# can_shield_simplified.net
KiCad netlist of a schematic drawn in EAGLE
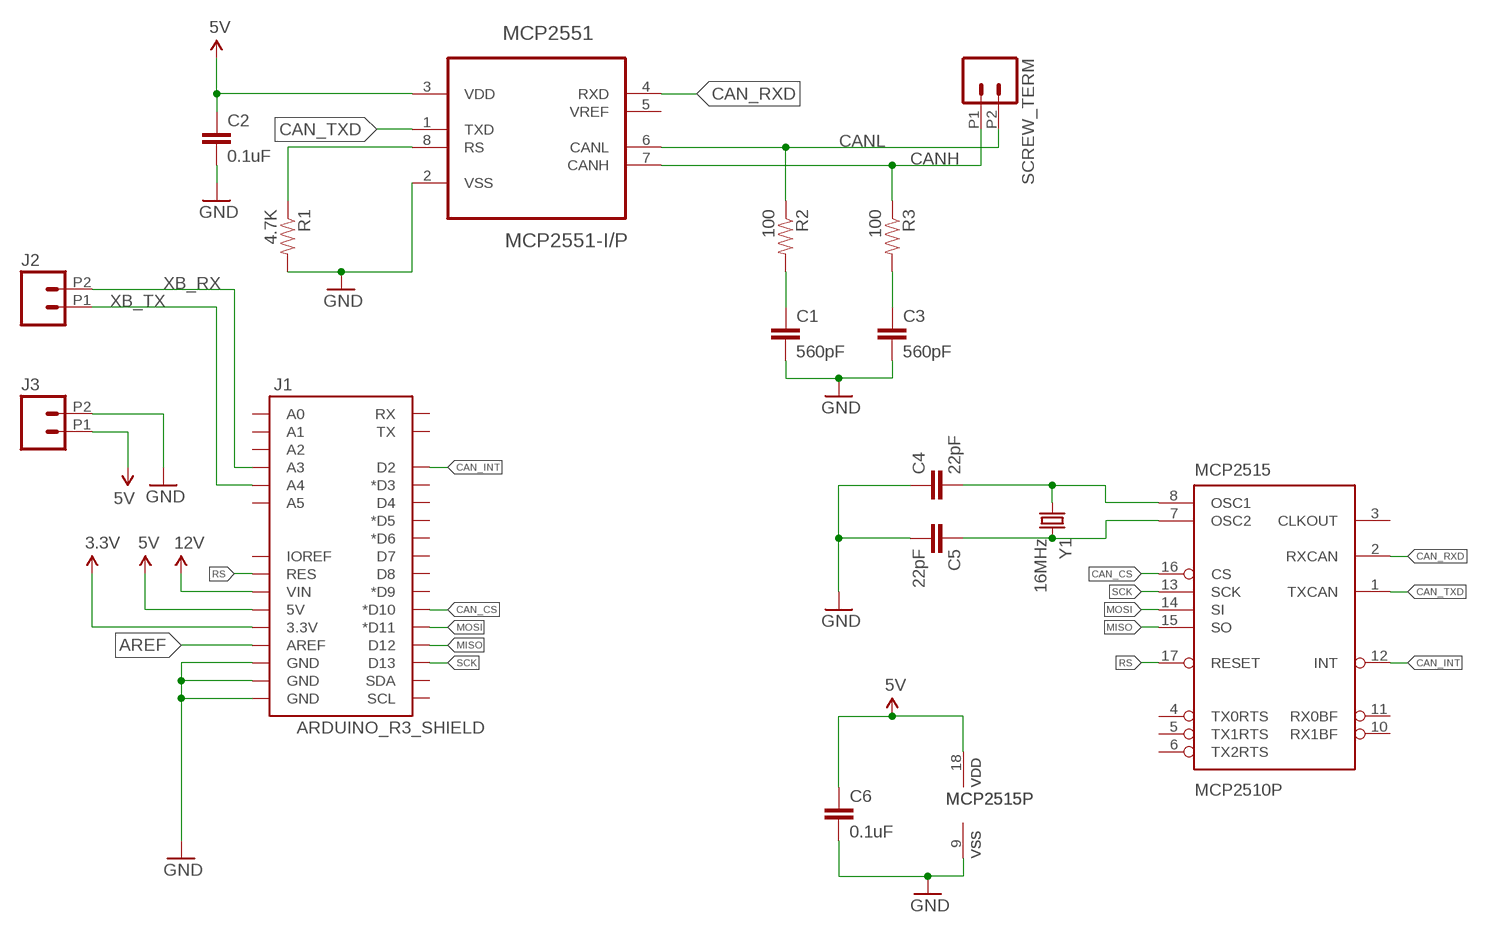
[diagram p0: schematic, sheet 1]

(export (version "E")
  (design (tool "Eeschema 10.0.6"))
  (components
    (comp (ref "C1")
      (value "560pF")
      (footprint "eagle-import:CAP-PTH-SMALL")
      (libsource (lib "eagle-import") (part "CAPPTH"))
    )
    (comp (ref "C2")
      (value "0.1uF")
      (footprint "eagle-import:CAP-PTH-SMALL")
      (libsource (lib "eagle-import") (part "CAPPTH"))
    )
    (comp (ref "C3")
      (value "560pF")
      (footprint "eagle-import:CAP-PTH-SMALL")
      (libsource (lib "eagle-import") (part "CAPPTH"))
    )
    (comp (ref "C4")
      (value "22pF")
      (footprint "eagle-import:CAP-PTH-SMALL")
      (libsource (lib "eagle-import") (part "CAPPTH"))
    )
    (comp (ref "C5")
      (value "22pF")
      (footprint "eagle-import:CAP-PTH-SMALL")
      (libsource (lib "eagle-import") (part "CAPPTH"))
    )
    (comp (ref "C6")
      (value "0.1uF")
      (footprint "eagle-import:CAP-PTH-SMALL")
      (libsource (lib "eagle-import") (part "CAPPTH"))
    )
    (comp (ref "J1")
      (value "ARDUINO_R3_SHIELD")
      (footprint "eagle-import:UNO_R3_SHIELD")
      (libsource (lib "eagle-import") (part "ARDUINO_R3_SHIELD"))
    )
    (comp (ref "J2")
      (value "M022.54MM_SCREWTERM")
      (footprint "eagle-import:1X02_2.54_SCREWTERM")
      (libsource (lib "eagle-import") (part "M022.54MM_SCREWTERM"))
    )
    (comp (ref "J3")
      (value "M022.54MM_SCREWTERM")
      (footprint "eagle-import:1X02_2.54_SCREWTERM")
      (libsource (lib "eagle-import") (part "M022.54MM_SCREWTERM"))
    )
    (comp (ref "MCP2515")
      (value "MCP2510P")
      (footprint "eagle-import:DIL18")
      (libsource (lib "eagle-import") (part "MCP2510P"))
    )
    (comp (ref "MCP2551")
      (value "MCP2551-I/P")
      (footprint "eagle-import:DIP254P762X432-8")
      (libsource (lib "eagle-import") (part "MCP2551-I/P"))
    )
    (comp (ref "R1")
      (value "4.7K")
      (footprint "eagle-import:AXIAL-0.3")
      (libsource (lib "eagle-import") (part "RESISTORAXIAL-0.3"))
    )
    (comp (ref "R2")
      (value "100")
      (footprint "eagle-import:AXIAL-0.3")
      (libsource (lib "eagle-import") (part "RESISTORAXIAL-0.3"))
    )
    (comp (ref "R3")
      (value "100")
      (footprint "eagle-import:AXIAL-0.3")
      (libsource (lib "eagle-import") (part "RESISTORAXIAL-0.3"))
    )
    (comp (ref "SCREW_TERM")
      (value "M022.54MM_SCREWTERM")
      (footprint "eagle-import:1X02_2.54_SCREWTERM")
      (libsource (lib "eagle-import") (part "M022.54MM_SCREWTERM"))
    )
    (comp (ref "Y1")
      (value "16MHz")
      (footprint "eagle-import:HC49US")
      (libsource (lib "eagle-import") (part "CRYSTALHC49US"))
    )
  )
  (nets
    (net (code "1") (name "/CANH") (class "Default")
      (node (ref "MCP2551") (pin "7") (pinfunction "CANH_7") (pintype "bidirectional"))
      (node (ref "R3") (pin "P$1") (pinfunction "1_P$1") (pintype "passive"))
      (node (ref "SCREW_TERM") (pin "P1") (pinfunction "1_P1") (pintype "passive"))
    )
    (net (code "2") (name "/CANL") (class "Default")
      (node (ref "MCP2551") (pin "6") (pinfunction "CANL_6") (pintype "bidirectional"))
      (node (ref "R2") (pin "P$1") (pinfunction "1_P$1") (pintype "passive"))
      (node (ref "SCREW_TERM") (pin "P2") (pinfunction "2_P2") (pintype "passive"))
    )
    (net (code "3") (name "/XB_RX") (class "Default")
      (node (ref "J1") (pin "A3") (pinfunction "A3_A3") (pintype "bidirectional"))
      (node (ref "J2") (pin "P2") (pinfunction "2_P2") (pintype "passive"))
    )
    (net (code "4") (name "/XB_TX") (class "Default")
      (node (ref "J1") (pin "A4") (pinfunction "A4_A4") (pintype "bidirectional"))
      (node (ref "J2") (pin "P1") (pinfunction "1_P1") (pintype "passive"))
    )
    (net (code "5") (name "3.3V") (class "Default")
      (node (ref "J1") (pin "3.3V") (pinfunction "3.3V_3.3V") (pintype "bidirectional"))
    )
    (net (code "6") (name "5V") (class "Default")
      (node (ref "C2") (pin "1") (pinfunction "1_1") (pintype "passive"))
      (node (ref "C6") (pin "1") (pinfunction "1_1") (pintype "passive"))
      (node (ref "J1") (pin "5V") (pinfunction "5V_5V") (pintype "bidirectional"))
      (node (ref "J3") (pin "P1") (pinfunction "1_P1") (pintype "passive"))
      (node (ref "MCP2515") (pin "18") (pinfunction "VDD_18") (pintype "power_in"))
      (node (ref "MCP2551") (pin "3") (pinfunction "VDD_3") (pintype "power_in"))
    )
    (net (code "7") (name "12V") (class "Default")
      (node (ref "J1") (pin "VIN") (pinfunction "VIN_VIN") (pintype "bidirectional"))
    )
    (net (code "8") (name "AREF") (class "Default")
      (node (ref "J1") (pin "AREF") (pinfunction "AREF_AREF") (pintype "bidirectional"))
    )
    (net (code "9") (name "CAN_CS") (class "Default")
      (node (ref "J1") (pin "D10") (pinfunction "*D10_D10") (pintype "bidirectional"))
      (node (ref "MCP2515") (pin "16") (pinfunction "CS_16") (pintype "input"))
    )
    (net (code "10") (name "CAN_INT") (class "Default")
      (node (ref "J1") (pin "D2") (pinfunction "D2_D2") (pintype "bidirectional"))
      (node (ref "MCP2515") (pin "12") (pinfunction "INT_12") (pintype "output"))
    )
    (net (code "11") (name "CAN_RXD") (class "Default")
      (node (ref "MCP2515") (pin "2") (pinfunction "RXCAN_2") (pintype "input"))
      (node (ref "MCP2551") (pin "4") (pinfunction "RXD_4") (pintype "output"))
    )
    (net (code "12") (name "CAN_TXD") (class "Default")
      (node (ref "MCP2515") (pin "1") (pinfunction "TXCAN_1") (pintype "output"))
      (node (ref "MCP2551") (pin "1") (pinfunction "TXD_1") (pintype "input"))
    )
    (net (code "13") (name "GND") (class "Default")
      (node (ref "C1") (pin "2") (pinfunction "2_2") (pintype "passive"))
      (node (ref "C2") (pin "2") (pinfunction "2_2") (pintype "passive"))
      (node (ref "C3") (pin "2") (pinfunction "2_2") (pintype "passive"))
      (node (ref "C4") (pin "1") (pinfunction "1_1") (pintype "passive"))
      (node (ref "C5") (pin "2") (pinfunction "2_2") (pintype "passive"))
      (node (ref "C6") (pin "2") (pinfunction "2_2") (pintype "passive"))
      (node (ref "J1") (pin "GND@0") (pinfunction "GND_GND@0") (pintype "bidirectional"))
      (node (ref "J1") (pin "GND@1") (pinfunction "GND_GND@1") (pintype "bidirectional"))
      (node (ref "J1") (pin "GND@2") (pinfunction "GND_GND@2") (pintype "bidirectional"))
      (node (ref "J3") (pin "P2") (pinfunction "2_P2") (pintype "passive"))
      (node (ref "MCP2515") (pin "9") (pinfunction "VSS_9") (pintype "power_in"))
      (node (ref "MCP2551") (pin "2") (pinfunction "VSS_2") (pintype "power_in"))
      (node (ref "R1") (pin "P$2") (pinfunction "2_P$2") (pintype "passive"))
    )
    (net (code "14") (name "MISO") (class "Default")
      (node (ref "J1") (pin "D12") (pinfunction "D12_D12") (pintype "bidirectional"))
      (node (ref "MCP2515") (pin "15") (pinfunction "SO_15") (pintype "output"))
    )
    (net (code "15") (name "MOSI") (class "Default")
      (node (ref "J1") (pin "D11") (pinfunction "*D11_D11") (pintype "bidirectional"))
      (node (ref "MCP2515") (pin "14") (pinfunction "SI_14") (pintype "input"))
    )
    (net (code "16") (name "Net-(MCP2515A-OSC1)") (class "Default")
      (node (ref "C4") (pin "2") (pinfunction "2_2") (pintype "passive"))
      (node (ref "MCP2515") (pin "8") (pinfunction "OSC1_8") (pintype "input"))
      (node (ref "Y1") (pin "1") (pinfunction "1_1") (pintype "passive"))
    )
    (net (code "17") (name "Net-(MCP2515A-OSC2)") (class "Default")
      (node (ref "C5") (pin "1") (pinfunction "1_1") (pintype "passive"))
      (node (ref "MCP2515") (pin "7") (pinfunction "OSC2_7") (pintype "output"))
      (node (ref "Y1") (pin "2") (pinfunction "2_2") (pintype "passive"))
    )
    (net (code "18") (name "Net-(MCP2551-RS)") (class "Default")
      (node (ref "MCP2551") (pin "8") (pinfunction "RS_8") (pintype "input"))
      (node (ref "R1") (pin "P$1") (pinfunction "1_P$1") (pintype "passive"))
    )
    (net (code "19") (name "Net-(R2-2)") (class "Default")
      (node (ref "C1") (pin "1") (pinfunction "1_1") (pintype "passive"))
      (node (ref "R2") (pin "P$2") (pinfunction "2_P$2") (pintype "passive"))
    )
    (net (code "20") (name "Net-(R3-2)") (class "Default")
      (node (ref "C3") (pin "1") (pinfunction "1_1") (pintype "passive"))
      (node (ref "R3") (pin "P$2") (pinfunction "2_P$2") (pintype "passive"))
    )
    (net (code "21") (name "RS") (class "Default")
      (node (ref "J1") (pin "RES") (pinfunction "RES_RES") (pintype "bidirectional"))
      (node (ref "MCP2515") (pin "17") (pinfunction "RESET_17") (pintype "input"))
    )
    (net (code "22") (name "SCK") (class "Default")
      (node (ref "J1") (pin "D13") (pinfunction "D13_D13") (pintype "bidirectional"))
      (node (ref "MCP2515") (pin "13") (pinfunction "SCK_13") (pintype "input"))
    )
    (net (code "23") (name "unconnected-(J1-*D3-PadD3)") (class "Default")
      (node (ref "J1") (pin "D3") (pinfunction "*D3_D3") (pintype "bidirectional"))
    )
    (net (code "24") (name "unconnected-(J1-*D5-PadD5)") (class "Default")
      (node (ref "J1") (pin "D5") (pinfunction "*D5_D5") (pintype "bidirectional"))
    )
    (net (code "25") (name "unconnected-(J1-*D6-PadD6)") (class "Default")
      (node (ref "J1") (pin "D6") (pinfunction "*D6_D6") (pintype "bidirectional"))
    )
    (net (code "26") (name "unconnected-(J1-*D9-PadD9)") (class "Default")
      (node (ref "J1") (pin "D9") (pinfunction "*D9_D9") (pintype "bidirectional"))
    )
    (net (code "27") (name "unconnected-(J1-PadA0)") (class "Default")
      (node (ref "J1") (pin "A0") (pinfunction "A0_A0") (pintype "bidirectional"))
    )
    (net (code "28") (name "unconnected-(J1-PadA1)") (class "Default")
      (node (ref "J1") (pin "A1") (pinfunction "A1_A1") (pintype "bidirectional"))
    )
    (net (code "29") (name "unconnected-(J1-PadA2)") (class "Default")
      (node (ref "J1") (pin "A2") (pinfunction "A2_A2") (pintype "bidirectional"))
    )
    (net (code "30") (name "unconnected-(J1-PadA5)") (class "Default")
      (node (ref "J1") (pin "A5") (pinfunction "A5_A5") (pintype "bidirectional"))
    )
    (net (code "31") (name "unconnected-(J1-PadD4)") (class "Default")
      (node (ref "J1") (pin "D4") (pinfunction "D4_D4") (pintype "bidirectional"))
    )
    (net (code "32") (name "unconnected-(J1-PadD7)") (class "Default")
      (node (ref "J1") (pin "D7") (pinfunction "D7_D7") (pintype "bidirectional"))
    )
    (net (code "33") (name "unconnected-(J1-PadD8)") (class "Default")
      (node (ref "J1") (pin "D8") (pinfunction "D8_D8") (pintype "bidirectional"))
    )
    (net (code "34") (name "unconnected-(J1-PadIOREF)") (class "Default")
      (node (ref "J1") (pin "IOREF") (pinfunction "IOREF_IOREF") (pintype "bidirectional"))
    )
    (net (code "35") (name "unconnected-(J1-PadRX)") (class "Default")
      (node (ref "J1") (pin "RX") (pinfunction "RX_RX") (pintype "bidirectional"))
    )
    (net (code "36") (name "unconnected-(J1-PadSCL)") (class "Default")
      (node (ref "J1") (pin "SCL") (pinfunction "SCL_SCL") (pintype "bidirectional"))
    )
    (net (code "37") (name "unconnected-(J1-PadSDA)") (class "Default")
      (node (ref "J1") (pin "SDA") (pinfunction "SDA_SDA") (pintype "bidirectional"))
    )
    (net (code "38") (name "unconnected-(J1-PadTX)") (class "Default")
      (node (ref "J1") (pin "TX") (pinfunction "TX_TX") (pintype "bidirectional"))
    )
    (net (code "39") (name "unconnected-(MCP2515A-CLKOUT-Pad3)") (class "Default")
      (node (ref "MCP2515") (pin "3") (pinfunction "CLKOUT_3") (pintype "output"))
    )
    (net (code "40") (name "unconnected-(MCP2515A-RX0BF-Pad11)") (class "Default")
      (node (ref "MCP2515") (pin "11") (pinfunction "RX0BF_11") (pintype "output"))
    )
    (net (code "41") (name "unconnected-(MCP2515A-RX1BF-Pad10)") (class "Default")
      (node (ref "MCP2515") (pin "10") (pinfunction "RX1BF_10") (pintype "output"))
    )
    (net (code "42") (name "unconnected-(MCP2515A-TX0RTS-Pad4)") (class "Default")
      (node (ref "MCP2515") (pin "4") (pinfunction "TX0RTS_4") (pintype "input"))
    )
    (net (code "43") (name "unconnected-(MCP2515A-TX1RTS-Pad5)") (class "Default")
      (node (ref "MCP2515") (pin "5") (pinfunction "TX1RTS_5") (pintype "input"))
    )
    (net (code "44") (name "unconnected-(MCP2515A-TX2RTS-Pad6)") (class "Default")
      (node (ref "MCP2515") (pin "6") (pinfunction "TX2RTS_6") (pintype "input"))
    )
    (net (code "45") (name "unconnected-(MCP2551-VREF-Pad5)") (class "Default")
      (node (ref "MCP2551") (pin "5") (pinfunction "VREF_5") (pintype "output"))
    )
  )
)
